# Sheet1.net
KiCad netlist of a schematic drawn in Altium Designer
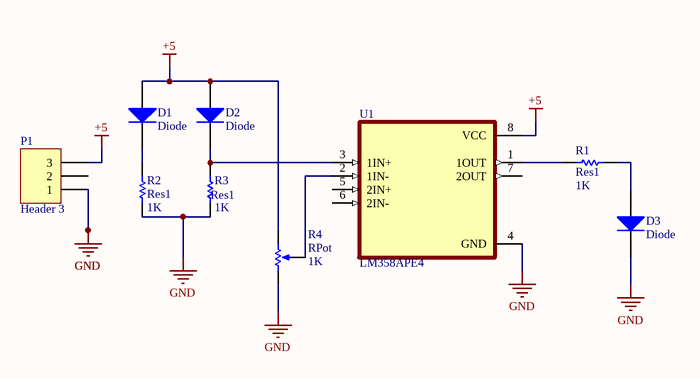
[diagram p0: Sheet1.SchDoc]

(export (version "E")
  (design (tool "Eeschema 10.0.6"))
  (components
    (comp (ref "D1")
      (value "Diode")
      (footprint "SMC")
      (description "Default Diode")
      (fields (field (name "PUBLISHER") "Altium Limited"))
      (libsource (lib "Miscellaneous Devices") (part "Diode"))
    )
    (comp (ref "D2")
      (value "Diode")
      (footprint "SMC")
      (description "Default Diode")
      (fields (field (name "PUBLISHER") "Altium Limited"))
      (libsource (lib "Miscellaneous Devices") (part "Diode"))
    )
    (comp (ref "D3")
      (value "Diode")
      (footprint "SMC")
      (description "Default Diode")
      (fields (field (name "PUBLISHER") "Altium Limited"))
      (libsource (lib "Miscellaneous Devices") (part "Diode"))
    )
    (comp (ref "P1")
      (value "Header 3")
      (footprint "HDR1X3")
      (description "Header, 3-Pin")
      (fields (field (name "PUBLISHER") "Altium Limited"))
      (libsource (lib "Miscellaneous Connectors") (part "Header 3"))
    )
    (comp (ref "R1")
      (value "Res1")
      (footprint "AXIAL-0.3")
      (description "Resistor")
      (fields (field (name "ALTIUM_VALUE") "1K") (field (name "PUBLISHER") "Altium Limited"))
      (libsource (lib "Miscellaneous Devices") (part "Res1"))
    )
    (comp (ref "R2")
      (value "Res1")
      (footprint "AXIAL-0.3")
      (description "Resistor")
      (fields (field (name "ALTIUM_VALUE") "1K") (field (name "PUBLISHER") "Altium Limited"))
      (libsource (lib "Miscellaneous Devices") (part "Res1"))
    )
    (comp (ref "R3")
      (value "Res1")
      (footprint "AXIAL-0.3")
      (description "Resistor")
      (fields (field (name "ALTIUM_VALUE") "1K") (field (name "PUBLISHER") "Altium Limited"))
      (libsource (lib "Miscellaneous Devices") (part "Res1"))
    )
    (comp (ref "R4")
      (value "RPot")
      (footprint "VR5")
      (description "Potentiometer")
      (fields (field (name "ALTIUM_VALUE") "1K") (field (name "PUBLISHER") "Altium Limited"))
      (libsource (lib "Miscellaneous Devices") (part "RPot"))
    )
    (comp (ref "U1")
      (value "LM358APE4")
      (footprint "DIP794W45P254L959H508Q8:DIP794W45P254L959H508Q8")
      (description "Dual, 30-V, 700-kHz operational amplifier")
      (fields (field (name "MF") "Texas Instruments"))
      (libsource (lib "LM358APE4") (part "LM358APE4"))
    )
  )
  (nets
    (net (code "1") (name "+5") (class "Default")
      (node (ref "D1") (pin "1") (pinfunction "A_1") (pintype "passive"))
      (node (ref "D2") (pin "1") (pinfunction "A_1") (pintype "passive"))
      (node (ref "P1") (pin "3") (pinfunction "3_3") (pintype "passive"))
      (node (ref "R4") (pin "2") (pinfunction "BOT_2") (pintype "passive"))
      (node (ref "U1") (pin "8") (pinfunction "VCC_8") (pintype "power_in"))
    )
    (net (code "2") (name "GND") (class "Default")
      (node (ref "D3") (pin "2") (pinfunction "K_2") (pintype "passive"))
      (node (ref "P1") (pin "1") (pinfunction "1_1") (pintype "passive"))
      (node (ref "R2") (pin "2") (pinfunction "2_2") (pintype "passive"))
      (node (ref "R3") (pin "2") (pinfunction "2_2") (pintype "passive"))
      (node (ref "R4") (pin "1") (pinfunction "TOP_1") (pintype "passive"))
      (node (ref "U1") (pin "4") (pinfunction "GND_4") (pintype "power_in"))
    )
    (net (code "3") (name "Net-(D1-K)") (class "Default")
      (node (ref "D1") (pin "2") (pinfunction "K_2") (pintype "passive"))
      (node (ref "R2") (pin "1") (pinfunction "1_1") (pintype "passive"))
    )
    (net (code "4") (name "Net-(D2-K)") (class "Default")
      (node (ref "D2") (pin "2") (pinfunction "K_2") (pintype "passive"))
      (node (ref "R3") (pin "1") (pinfunction "1_1") (pintype "passive"))
      (node (ref "U1") (pin "3") (pinfunction "1IN+_3") (pintype "input"))
    )
    (net (code "5") (name "Net-(D3-A)") (class "Default")
      (node (ref "D3") (pin "1") (pinfunction "A_1") (pintype "passive"))
      (node (ref "R1") (pin "2") (pinfunction "2_2") (pintype "passive"))
    )
    (net (code "6") (name "Net-(R4-TAP)") (class "Default")
      (node (ref "R4") (pin "3") (pinfunction "TAP_3") (pintype "passive"))
      (node (ref "U1") (pin "2") (pinfunction "1IN-_2") (pintype "input"))
    )
    (net (code "7") (name "Net-(U1-1OUT)") (class "Default")
      (node (ref "R1") (pin "1") (pinfunction "1_1") (pintype "passive"))
      (node (ref "U1") (pin "1") (pinfunction "1OUT_1") (pintype "output"))
    )
    (net (code "8") (name "unconnected-(P1-Pad2)") (class "Default")
      (node (ref "P1") (pin "2") (pinfunction "2_2") (pintype "passive"))
    )
    (net (code "9") (name "unconnected-(U1-2IN+-Pad5)") (class "Default")
      (node (ref "U1") (pin "5") (pinfunction "2IN+_5") (pintype "input"))
    )
    (net (code "10") (name "unconnected-(U1-2IN--Pad6)") (class "Default")
      (node (ref "U1") (pin "6") (pinfunction "2IN-_6") (pintype "input"))
    )
    (net (code "11") (name "unconnected-(U1-2OUT-Pad7)") (class "Default")
      (node (ref "U1") (pin "7") (pinfunction "2OUT_7") (pintype "output"))
    )
  )
)
